# 05_USB_PORTS.net
KiCad netlist of a schematic drawn in Altium Designer
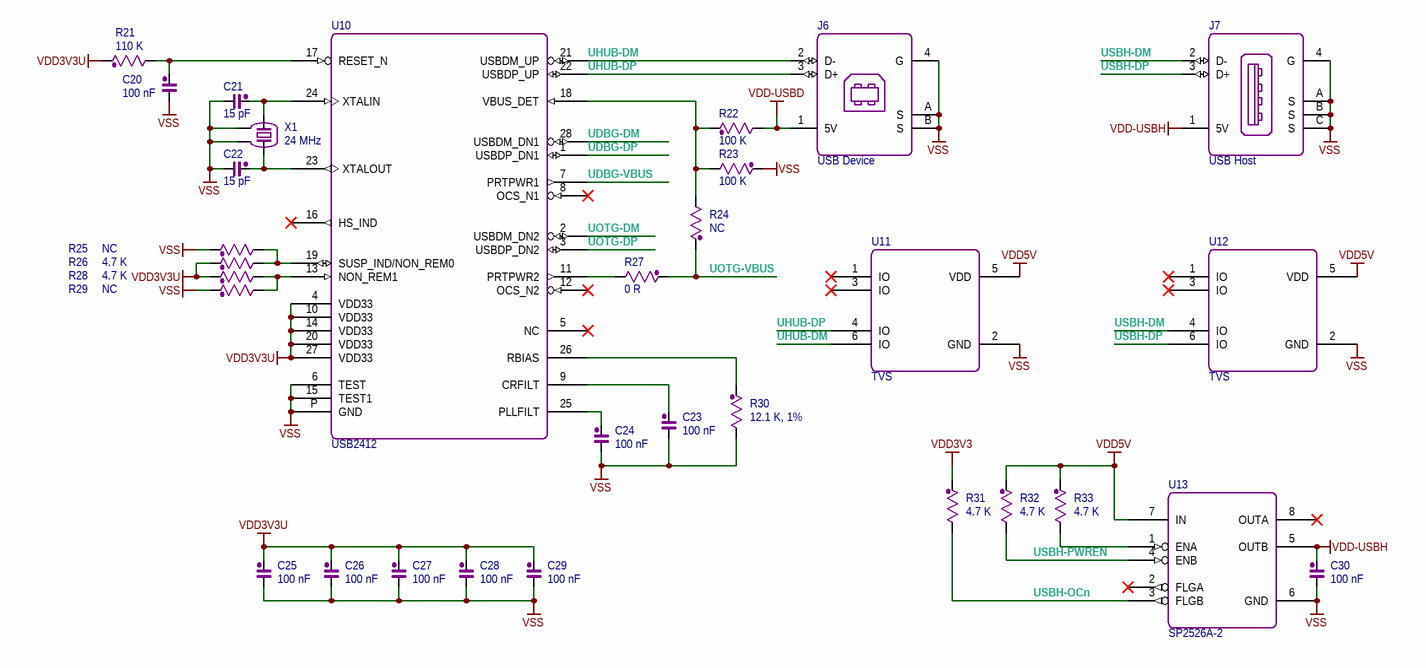
[diagram p0: 05_USB_PORTS.SchDoc]

(export (version "E")
  (design (tool "Eeschema 10.0.6"))
  (components
    (comp (ref "C20")
      (value "100 nF")
      (footprint "0402A1")
      (description "Normal Capacitor")
      (fields
        (field (name "PARTNUMBER") "0")
        (field (name "PUBLISHER") "Cowin")
        (field (name "DESIGNER") "shyul")
      )
      (libsource (lib "Basc_1_Passive") (part "CAP"))
    )
    (comp (ref "C21")
      (value "15 pF")
      (footprint "0402A1")
      (description "Normal Capacitor")
      (fields
        (field (name "PARTNUMBER") "0")
        (field (name "PUBLISHER") "Cowin")
        (field (name "DESIGNER") "shyul")
      )
      (libsource (lib "") (part "CAP_1"))
    )
    (comp (ref "C22")
      (value "15 pF")
      (footprint "0402A1")
      (description "Normal Capacitor")
      (fields
        (field (name "PARTNUMBER") "0")
        (field (name "PUBLISHER") "Cowin")
        (field (name "DESIGNER") "shyul")
      )
      (libsource (lib "") (part "CAP_1"))
    )
    (comp (ref "C23")
      (value "100 nF")
      (footprint "0402A1")
      (description "Normal Capacitor")
      (fields
        (field (name "PARTNUMBER") "0")
        (field (name "PUBLISHER") "Cowin")
        (field (name "DESIGNER") "shyul")
      )
      (libsource (lib "Basc_1_Passive") (part "CAP"))
    )
    (comp (ref "C24")
      (value "100 nF")
      (footprint "0402A1")
      (description "Normal Capacitor")
      (fields
        (field (name "PARTNUMBER") "0")
        (field (name "PUBLISHER") "Cowin")
        (field (name "DESIGNER") "shyul")
      )
      (libsource (lib "Basc_1_Passive") (part "CAP"))
    )
    (comp (ref "C25")
      (value "100 nF")
      (footprint "0402A1")
      (description "Normal Capacitor")
      (fields
        (field (name "PARTNUMBER") "0")
        (field (name "PUBLISHER") "Cowin")
        (field (name "DESIGNER") "shyul")
      )
      (libsource (lib "Basc_1_Passive") (part "CAP"))
    )
    (comp (ref "C26")
      (value "100 nF")
      (footprint "0402A1")
      (description "Normal Capacitor")
      (fields
        (field (name "PARTNUMBER") "0")
        (field (name "PUBLISHER") "Cowin")
        (field (name "DESIGNER") "shyul")
      )
      (libsource (lib "Basc_1_Passive") (part "CAP"))
    )
    (comp (ref "C27")
      (value "100 nF")
      (footprint "0402A1")
      (description "Normal Capacitor")
      (fields
        (field (name "PARTNUMBER") "0")
        (field (name "PUBLISHER") "Cowin")
        (field (name "DESIGNER") "shyul")
      )
      (libsource (lib "Basc_1_Passive") (part "CAP"))
    )
    (comp (ref "C28")
      (value "100 nF")
      (footprint "0402A1")
      (description "Normal Capacitor")
      (fields
        (field (name "PARTNUMBER") "0")
        (field (name "PUBLISHER") "Cowin")
        (field (name "DESIGNER") "shyul")
      )
      (libsource (lib "Basc_1_Passive") (part "CAP"))
    )
    (comp (ref "C29")
      (value "100 nF")
      (footprint "0402A1")
      (description "Normal Capacitor")
      (fields
        (field (name "PARTNUMBER") "0")
        (field (name "PUBLISHER") "Cowin")
        (field (name "DESIGNER") "shyul")
      )
      (libsource (lib "Basc_1_Passive") (part "CAP"))
    )
    (comp (ref "C30")
      (value "100 nF")
      (footprint "0603A1")
      (description "Normal Capacitor")
      (fields
        (field (name "PARTNUMBER") "0")
        (field (name "PUBLISHER") "Cowin")
        (field (name "DESIGNER") "shyul")
      )
      (libsource (lib "Basc_1_Passive") (part "CAP"))
    )
    (comp (ref "J6")
      (value "USB Device")
      (footprint "USBD1A")
      (description "USB Device Jack")
      (libsource (lib "Connector_1_General") (part "USBD_JACK"))
    )
    (comp (ref "J7")
      (value "USB Host")
      (footprint "USBH1C")
      (description "USB Host Jack")
      (libsource (lib "Connector_1_General") (part "USBH_JACK"))
    )
    (comp (ref "R21")
      (value "110 K")
      (footprint "0402A2")
      (description "Normal Resistor")
      (fields
        (field (name "PARTNUMBER") "0")
        (field (name "DESIGNER") "shyul")
        (field (name "PUBLISHER") "Cowin")
      )
      (libsource (lib "Basc_1_Passive") (part "RES"))
    )
    (comp (ref "R22")
      (value "100 K")
      (footprint "0603A2")
      (description "Normal Resistor")
      (fields
        (field (name "PARTNUMBER") "0")
        (field (name "DESIGNER") "shyul")
        (field (name "PUBLISHER") "Cowin")
      )
      (libsource (lib "Basc_1_Passive") (part "RES"))
    )
    (comp (ref "R23")
      (value "100 K")
      (footprint "0603A2")
      (description "Normal Resistor")
      (fields
        (field (name "PARTNUMBER") "0")
        (field (name "DESIGNER") "shyul")
        (field (name "PUBLISHER") "Cowin")
      )
      (libsource (lib "Basc_1_Passive") (part "RES"))
    )
    (comp (ref "R24")
      (value "NC")
      (footprint "0603A2")
      (description "Normal Resistor")
      (fields
        (field (name "PARTNUMBER") "0")
        (field (name "DESIGNER") "shyul")
        (field (name "PUBLISHER") "Cowin")
      )
      (libsource (lib "Basc_1_Passive") (part "RES"))
    )
    (comp (ref "R25")
      (value "NC")
      (footprint "0402A2")
      (description "Normal Resistor")
      (fields
        (field (name "PARTNUMBER") "0")
        (field (name "DESIGNER") "shyul")
        (field (name "PUBLISHER") "Cowin")
      )
      (libsource (lib "Basc_1_Passive") (part "RES"))
    )
    (comp (ref "R26")
      (value "4.7 K")
      (footprint "0402A2")
      (description "Normal Resistor")
      (fields
        (field (name "PARTNUMBER") "0")
        (field (name "DESIGNER") "shyul")
        (field (name "PUBLISHER") "Cowin")
      )
      (libsource (lib "Basc_1_Passive") (part "RES"))
    )
    (comp (ref "R27")
      (value "0 R")
      (footprint "0603A2")
      (description "Normal Resistor")
      (fields
        (field (name "PARTNUMBER") "0")
        (field (name "DESIGNER") "shyul")
        (field (name "PUBLISHER") "Cowin")
      )
      (libsource (lib "Basc_1_Passive") (part "RES"))
    )
    (comp (ref "R28")
      (value "4.7 K")
      (footprint "0402A2")
      (description "Normal Resistor")
      (fields
        (field (name "PARTNUMBER") "0")
        (field (name "DESIGNER") "shyul")
        (field (name "PUBLISHER") "Cowin")
      )
      (libsource (lib "Basc_1_Passive") (part "RES"))
    )
    (comp (ref "R29")
      (value "NC")
      (footprint "0402A2")
      (description "Normal Resistor")
      (fields
        (field (name "PARTNUMBER") "0")
        (field (name "DESIGNER") "shyul")
        (field (name "PUBLISHER") "Cowin")
      )
      (libsource (lib "Basc_1_Passive") (part "RES"))
    )
    (comp (ref "R30")
      (value "12.1 K, 1%")
      (footprint "0402A2")
      (description "Normal Resistor")
      (fields
        (field (name "PARTNUMBER") "0")
        (field (name "DESIGNER") "shyul")
        (field (name "PUBLISHER") "Cowin")
      )
      (libsource (lib "Basc_1_Passive") (part "RES"))
    )
    (comp (ref "R31")
      (value "4.7 K")
      (footprint "0603A2")
      (description "Normal Resistor")
      (fields
        (field (name "PARTNUMBER") "0")
        (field (name "DESIGNER") "shyul")
        (field (name "PUBLISHER") "Cowin")
      )
      (libsource (lib "Basc_1_Passive") (part "RES"))
    )
    (comp (ref "R32")
      (value "4.7 K")
      (footprint "0603A2")
      (description "Normal Resistor")
      (fields
        (field (name "PARTNUMBER") "0")
        (field (name "DESIGNER") "shyul")
        (field (name "PUBLISHER") "Cowin")
      )
      (libsource (lib "Basc_1_Passive") (part "RES"))
    )
    (comp (ref "R33")
      (value "4.7 K")
      (footprint "0603A2")
      (description "Normal Resistor")
      (fields
        (field (name "PARTNUMBER") "0")
        (field (name "DESIGNER") "shyul")
        (field (name "PUBLISHER") "Cowin")
      )
      (libsource (lib "Basc_1_Passive") (part "RES"))
    )
    (comp (ref "U10")
      (value "USB2412")
      (footprint "QFN-5-28")
      (description "Embedded USB Hub")
      (fields
        (field (name "PARTNUMBER") "USB2412-DZK")
        (field (name "PUBLISHER") "Cowin")
        (field (name "DESIGNER") "shyul")
      )
      (libsource (lib "PCB_MDB-U01") (part "USB2412"))
    )
    (comp (ref "U11")
      (value "TVS")
      (footprint "SOT-23-6")
      (description "4-way TVS Diodes")
      (fields
        (field (name "PARTNUMBER") "LXES2SBAA4-016")
        (field (name "PUBLISHER") "Cowin")
        (field (name "DESIGNER") "shyul")
      )
      (libsource (lib "Basc_2_EMI_Protection") (part "ESD_4A"))
    )
    (comp (ref "U12")
      (value "TVS")
      (footprint "SOT-23-6")
      (description "4-way TVS Diodes")
      (fields
        (field (name "PARTNUMBER") "LXES2SBAA4-016")
        (field (name "PUBLISHER") "Cowin")
        (field (name "DESIGNER") "shyul")
      )
      (libsource (lib "Basc_2_EMI_Protection") (part "ESD_4A"))
    )
    (comp (ref "U13")
      (value "SP2526A-2")
      (footprint "SOIC-8S")
      (description "Power Switch")
      (fields
        (field (name "PARTNUMBER") "SP2526A-2EN")
        (field (name "PUBLISHER") "Cowin")
        (field (name "DESIGNER") "shyul")
      )
      (libsource (lib "PCB_MDB-U01") (part "SP2526A-2"))
    )
    (comp (ref "X1")
      (value "24 MHz")
      (footprint "OSC_4A_S_3225")
      (description "Crystal")
      (fields
        (field (name "PARTNUMBER") "0")
        (field (name "PUBLISHER") "Cowin")
        (field (name "DESIGNER") "shyul")
      )
      (libsource (lib "Basc_4_Other") (part "OSC_2B"))
    )
  )
  (nets
    (net (code "1") (name "/UDBG-DM") (class "Default")
      (node (ref "U10") (pin "28") (pinfunction "USBDM_DN1_28") (pintype "bidirectional"))
    )
    (net (code "2") (name "/UDBG-DP") (class "Default")
      (node (ref "U10") (pin "1") (pinfunction "USBDP_DN1_1") (pintype "bidirectional"))
    )
    (net (code "3") (name "/UDBG-VBUS") (class "Default")
      (node (ref "U10") (pin "7") (pinfunction "PRTPWR1_7") (pintype "output"))
    )
    (net (code "4") (name "/UHUB-DM") (class "Default")
      (node (ref "J6") (pin "2") (pinfunction "D-_2") (pintype "bidirectional"))
      (node (ref "U10") (pin "21") (pinfunction "USBDM_UP_21") (pintype "bidirectional"))
      (node (ref "U11") (pin "6") (pinfunction "IO_6") (pintype "passive"))
    )
    (net (code "5") (name "/UHUB-DP") (class "Default")
      (node (ref "J6") (pin "3") (pinfunction "D+_3") (pintype "bidirectional"))
      (node (ref "U10") (pin "22") (pinfunction "USBDP_UP_22") (pintype "bidirectional"))
      (node (ref "U11") (pin "4") (pinfunction "IO_4") (pintype "passive"))
    )
    (net (code "6") (name "/UOTG-DM") (class "Default")
      (node (ref "U10") (pin "2") (pinfunction "USBDM_DN2_2") (pintype "bidirectional"))
    )
    (net (code "7") (name "/UOTG-DP") (class "Default")
      (node (ref "U10") (pin "3") (pinfunction "USBDP_DN2_3") (pintype "bidirectional"))
    )
    (net (code "8") (name "/UOTG-VBUS") (class "Default")
      (node (ref "R24") (pin "2") (pinfunction "2_2") (pintype "passive"))
      (node (ref "R27") (pin "2") (pinfunction "2_2") (pintype "passive"))
    )
    (net (code "9") (name "/USBH-DM") (class "Default")
      (node (ref "J7") (pin "2") (pinfunction "D-_2") (pintype "bidirectional"))
      (node (ref "U12") (pin "4") (pinfunction "IO_4") (pintype "passive"))
    )
    (net (code "10") (name "/USBH-DP") (class "Default")
      (node (ref "J7") (pin "3") (pinfunction "D+_3") (pintype "bidirectional"))
      (node (ref "U12") (pin "6") (pinfunction "IO_6") (pintype "passive"))
    )
    (net (code "11") (name "/USBH-OCn") (class "Default")
      (node (ref "R31") (pin "1") (pinfunction "1_1") (pintype "passive"))
      (node (ref "U13") (pin "3") (pinfunction "FLGB_3") (pintype "output"))
    )
    (net (code "12") (name "/USBH-PWREN") (class "Default")
      (node (ref "R32") (pin "1") (pinfunction "1_1") (pintype "passive"))
      (node (ref "U13") (pin "4") (pinfunction "ENB_4") (pintype "input"))
    )
    (net (code "13") (name "Net-(U10-CRFILT)") (class "Default")
      (node (ref "C23") (pin "2") (pinfunction "2_2") (pintype "passive"))
      (node (ref "U10") (pin "9") (pinfunction "CRFILT_9") (pintype "passive"))
    )
    (net (code "14") (name "Net-(U10-NON_REM1)") (class "Default")
      (node (ref "R28") (pin "1") (pinfunction "1_1") (pintype "passive"))
      (node (ref "R29") (pin "1") (pinfunction "1_1") (pintype "passive"))
      (node (ref "U10") (pin "13") (pinfunction "NON_REM1_13") (pintype "input"))
    )
    (net (code "15") (name "Net-(U10-PLLFILT)") (class "Default")
      (node (ref "C24") (pin "2") (pinfunction "2_2") (pintype "passive"))
      (node (ref "U10") (pin "25") (pinfunction "PLLFILT_25") (pintype "passive"))
    )
    (net (code "16") (name "Net-(U10-PRTPWR2)") (class "Default")
      (node (ref "R27") (pin "1") (pinfunction "1_1") (pintype "passive"))
      (node (ref "U10") (pin "11") (pinfunction "PRTPWR2_11") (pintype "output"))
    )
    (net (code "17") (name "Net-(U10-RBIAS)") (class "Default")
      (node (ref "R30") (pin "2") (pinfunction "2_2") (pintype "passive"))
      (node (ref "U10") (pin "26") (pinfunction "RBIAS_26") (pintype "passive"))
    )
    (net (code "18") (name "Net-(U10-RESET_N)") (class "Default")
      (node (ref "C20") (pin "2") (pinfunction "2_2") (pintype "passive"))
      (node (ref "R21") (pin "1") (pinfunction "1_1") (pintype "passive"))
      (node (ref "U10") (pin "17") (pinfunction "RESET_N_17") (pintype "input"))
    )
    (net (code "19") (name "Net-(U10-SUSP_IND{slash}NON_REM0)") (class "Default")
      (node (ref "R25") (pin "1") (pinfunction "1_1") (pintype "passive"))
      (node (ref "R26") (pin "1") (pinfunction "1_1") (pintype "passive"))
      (node (ref "U10") (pin "19") (pinfunction "SUSP_IND/NON_REM0_19") (pintype "bidirectional"))
    )
    (net (code "20") (name "Net-(U10-VBUS_DET)") (class "Default")
      (node (ref "R22") (pin "2") (pinfunction "2_2") (pintype "passive"))
      (node (ref "R23") (pin "1") (pinfunction "1_1") (pintype "passive"))
      (node (ref "R24") (pin "1") (pinfunction "1_1") (pintype "passive"))
      (node (ref "U10") (pin "18") (pinfunction "VBUS_DET_18") (pintype "input"))
    )
    (net (code "21") (name "Net-(U10-XTALIN)") (class "Default")
      (node (ref "C21") (pin "2") (pinfunction "2_2") (pintype "passive"))
      (node (ref "U10") (pin "24") (pinfunction "XTALIN_24") (pintype "input"))
      (node (ref "X1") (pin "3") (pinfunction "3_3") (pintype "passive"))
    )
    (net (code "22") (name "Net-(U10-XTALOUT)") (class "Default")
      (node (ref "C22") (pin "2") (pinfunction "2_2") (pintype "passive"))
      (node (ref "U10") (pin "23") (pinfunction "XTALOUT_23") (pintype "output"))
      (node (ref "X1") (pin "1") (pinfunction "1_1") (pintype "passive"))
    )
    (net (code "23") (name "Net-(U13-ENA)") (class "Default")
      (node (ref "R33") (pin "1") (pinfunction "1_1") (pintype "passive"))
      (node (ref "U13") (pin "1") (pinfunction "ENA_1") (pintype "input"))
    )
    (net (code "24") (name "VDD-USBD") (class "Default")
      (node (ref "J6") (pin "1") (pinfunction "5V_1") (pintype "power_in"))
      (node (ref "R22") (pin "1") (pinfunction "1_1") (pintype "passive"))
    )
    (net (code "25") (name "VDD-USBH") (class "Default")
      (node (ref "C30") (pin "2") (pinfunction "2_2") (pintype "passive"))
      (node (ref "J7") (pin "1") (pinfunction "5V_1") (pintype "passive"))
      (node (ref "U13") (pin "5") (pinfunction "OUTB_5") (pintype "power_in"))
    )
    (net (code "26") (name "VDD3V3") (class "Default")
      (node (ref "R31") (pin "2") (pinfunction "2_2") (pintype "passive"))
    )
    (net (code "27") (name "VDD3V3U") (class "Default")
      (node (ref "C25") (pin "2") (pinfunction "2_2") (pintype "passive"))
      (node (ref "C26") (pin "2") (pinfunction "2_2") (pintype "passive"))
      (node (ref "C27") (pin "2") (pinfunction "2_2") (pintype "passive"))
      (node (ref "C28") (pin "2") (pinfunction "2_2") (pintype "passive"))
      (node (ref "C29") (pin "2") (pinfunction "2_2") (pintype "passive"))
      (node (ref "R21") (pin "2") (pinfunction "2_2") (pintype "passive"))
      (node (ref "R26") (pin "2") (pinfunction "2_2") (pintype "passive"))
      (node (ref "R28") (pin "2") (pinfunction "2_2") (pintype "passive"))
      (node (ref "U10") (pin "10") (pinfunction "VDD33_10") (pintype "passive"))
      (node (ref "U10") (pin "14") (pinfunction "VDD33_14") (pintype "passive"))
      (node (ref "U10") (pin "20") (pinfunction "VDD33_20") (pintype "passive"))
      (node (ref "U10") (pin "27") (pinfunction "VDD33_27") (pintype "passive"))
      (node (ref "U10") (pin "4") (pinfunction "VDD33_4") (pintype "passive"))
    )
    (net (code "28") (name "VDD5V") (class "Default")
      (node (ref "R32") (pin "2") (pinfunction "2_2") (pintype "passive"))
      (node (ref "R33") (pin "2") (pinfunction "2_2") (pintype "passive"))
      (node (ref "U11") (pin "5") (pinfunction "VDD_5") (pintype "power_in"))
      (node (ref "U12") (pin "5") (pinfunction "VDD_5") (pintype "power_in"))
      (node (ref "U13") (pin "7") (pinfunction "IN_7") (pintype "passive"))
    )
    (net (code "29") (name "VSS") (class "Default")
      (node (ref "C20") (pin "1") (pinfunction "1_1") (pintype "passive"))
      (node (ref "C21") (pin "1") (pinfunction "1_1") (pintype "passive"))
      (node (ref "C22") (pin "1") (pinfunction "1_1") (pintype "passive"))
      (node (ref "C23") (pin "1") (pinfunction "1_1") (pintype "passive"))
      (node (ref "C24") (pin "1") (pinfunction "1_1") (pintype "passive"))
      (node (ref "C25") (pin "1") (pinfunction "1_1") (pintype "passive"))
      (node (ref "C26") (pin "1") (pinfunction "1_1") (pintype "passive"))
      (node (ref "C27") (pin "1") (pinfunction "1_1") (pintype "passive"))
      (node (ref "C28") (pin "1") (pinfunction "1_1") (pintype "passive"))
      (node (ref "C29") (pin "1") (pinfunction "1_1") (pintype "passive"))
      (node (ref "C30") (pin "1") (pinfunction "1_1") (pintype "passive"))
      (node (ref "J6") (pin "4") (pinfunction "G_4") (pintype "passive"))
      (node (ref "J6") (pin "A") (pinfunction "S_A") (pintype "passive"))
      (node (ref "J6") (pin "B") (pinfunction "S_B") (pintype "passive"))
      (node (ref "J7") (pin "4") (pinfunction "G_4") (pintype "passive"))
      (node (ref "J7") (pin "A") (pinfunction "S_A") (pintype "passive"))
      (node (ref "J7") (pin "B") (pinfunction "S_B") (pintype "passive"))
      (node (ref "J7") (pin "C") (pinfunction "S_C") (pintype "passive"))
      (node (ref "R23") (pin "2") (pinfunction "2_2") (pintype "passive"))
      (node (ref "R25") (pin "2") (pinfunction "2_2") (pintype "passive"))
      (node (ref "R29") (pin "2") (pinfunction "2_2") (pintype "passive"))
      (node (ref "R30") (pin "1") (pinfunction "1_1") (pintype "passive"))
      (node (ref "U10") (pin "15") (pinfunction "TEST1_15") (pintype "passive"))
      (node (ref "U10") (pin "6") (pinfunction "TEST_6") (pintype "passive"))
      (node (ref "U10") (pin "P") (pinfunction "GND_P") (pintype "passive"))
      (node (ref "U11") (pin "2") (pinfunction "GND_2") (pintype "power_in"))
      (node (ref "U12") (pin "2") (pinfunction "GND_2") (pintype "power_in"))
      (node (ref "U13") (pin "6") (pinfunction "GND_6") (pintype "passive"))
      (node (ref "X1") (pin "2") (pinfunction "2_2") (pintype "passive"))
      (node (ref "X1") (pin "4") (pinfunction "4_4") (pintype "passive"))
    )
    (net (code "30") (name "unconnected-(U10-HS_IND-Pad16)") (class "Default")
      (node (ref "U10") (pin "16") (pinfunction "HS_IND_16") (pintype "output+no_connect"))
    )
    (net (code "31") (name "unconnected-(U10-NC-Pad5)") (class "Default")
      (node (ref "U10") (pin "5") (pinfunction "NC_5") (pintype "passive+no_connect"))
    )
    (net (code "32") (name "unconnected-(U10-OCS_N1-Pad8)") (class "Default")
      (node (ref "U10") (pin "8") (pinfunction "OCS_N1_8") (pintype "input+no_connect"))
    )
    (net (code "33") (name "unconnected-(U10-OCS_N2-Pad12)") (class "Default")
      (node (ref "U10") (pin "12") (pinfunction "OCS_N2_12") (pintype "input+no_connect"))
    )
    (net (code "34") (name "unconnected-(U11-IO-Pad1)") (class "Default")
      (node (ref "U11") (pin "1") (pinfunction "IO_1") (pintype "passive+no_connect"))
    )
    (net (code "35") (name "unconnected-(U11-IO-Pad3)") (class "Default")
      (node (ref "U11") (pin "3") (pinfunction "IO_3") (pintype "passive+no_connect"))
    )
    (net (code "36") (name "unconnected-(U12-IO-Pad1)") (class "Default")
      (node (ref "U12") (pin "1") (pinfunction "IO_1") (pintype "passive+no_connect"))
    )
    (net (code "37") (name "unconnected-(U12-IO-Pad3)") (class "Default")
      (node (ref "U12") (pin "3") (pinfunction "IO_3") (pintype "passive+no_connect"))
    )
    (net (code "38") (name "unconnected-(U13-FLGA-Pad2)") (class "Default")
      (node (ref "U13") (pin "2") (pinfunction "FLGA_2") (pintype "output+no_connect"))
    )
    (net (code "39") (name "unconnected-(U13-OUTA-Pad8)") (class "Default")
      (node (ref "U13") (pin "8") (pinfunction "OUTA_8") (pintype "power_in+no_connect"))
    )
  )
)
